# Pinguino-PIC18.net
KiCad netlist of a schematic drawn in EAGLE
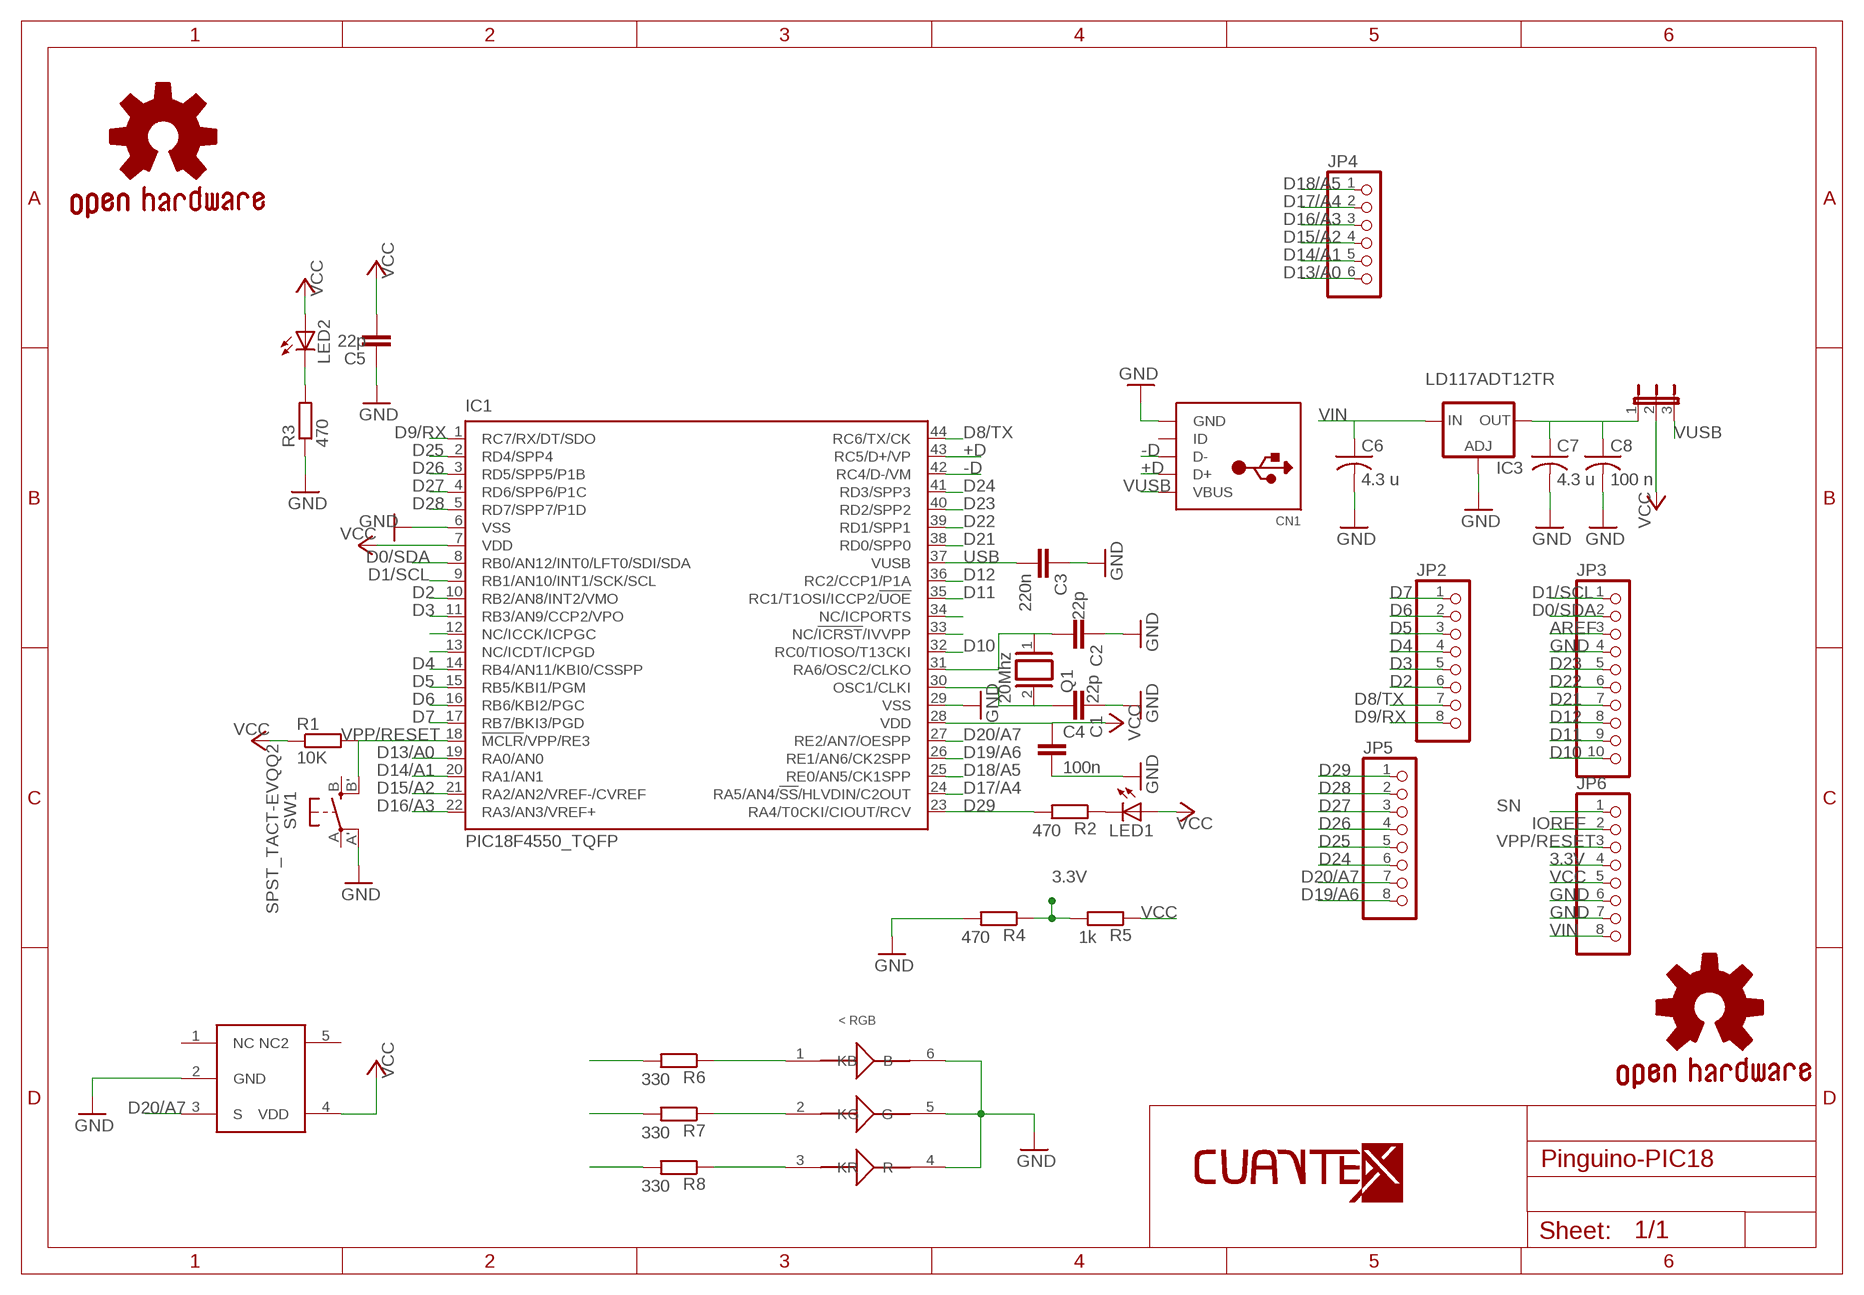
[diagram p0: schematic, sheet 1]

(export (version "E")
  (design (tool "Eeschema 10.0.6"))
  (components
    (comp (ref "C1")
      (value "22p")
      (footprint "eagle-import:C0603")
      (libsource (lib "eagle-import") (part "CC0603"))
    )
    (comp (ref "C2")
      (value "22p")
      (footprint "eagle-import:C0603")
      (libsource (lib "eagle-import") (part "CC0603"))
    )
    (comp (ref "C3")
      (value "220n")
      (footprint "eagle-import:C0603")
      (libsource (lib "eagle-import") (part "CC0603"))
    )
    (comp (ref "C4")
      (value "100n")
      (footprint "eagle-import:C0603")
      (libsource (lib "eagle-import") (part "CC0603"))
    )
    (comp (ref "C5")
      (value "22p")
      (footprint "eagle-import:C0603")
      (libsource (lib "eagle-import") (part "CC0603"))
    )
    (comp (ref "C6")
      (value "4.3 u")
      (footprint "eagle-import:C1206K")
      (libsource (lib "eagle-import") (part "C-USC1206K"))
    )
    (comp (ref "C7")
      (value "4.3 u")
      (footprint "eagle-import:C1206K")
      (libsource (lib "eagle-import") (part "C-USC1206K"))
    )
    (comp (ref "C8")
      (value "100 n")
      (footprint "eagle-import:C0603K")
      (libsource (lib "eagle-import") (part "C-USC0603K"))
    )
    (comp (ref "CN1")
      (value "USBMINIB")
      (footprint "eagle-import:USB-MINIB")
      (libsource (lib "eagle-import") (part "USBMINIB"))
    )
    (comp (ref "GOLD_ORB_SM1")
      (value "OSHWLOGO_GOLD_ORB_MED")
      (footprint "eagle-import:OSHW1")
      (libsource (lib "eagle-import") (part "OSHWLOGO_GOLD_ORB_MED"))
    )
    (comp (ref "GOLD_ORB_SM2")
      (value "OSHWLOGO_GOLD_ORB_SM")
      (footprint "eagle-import:OSHW2")
      (libsource (lib "eagle-import") (part "OSHWLOGO_GOLD_ORB_SM"))
    )
    (comp (ref "IC1")
      (value "PIC18F4550_TQFP")
      (footprint "eagle-import:TQFP44")
      (fields (field (name "MF") "MICROCHIP") (field (name "MPN") "PIC18F4550-I/PT"))
      (libsource (lib "eagle-import") (part "PIC18F4_TQFP550"))
    )
    (comp (ref "IC3")
      (value "LD117ADT12TR")
      (footprint "eagle-import:DPACK")
      (libsource (lib "eagle-import") (part "LD117A?DT12TR"))
    )
    (comp (ref "JP1")
      (value "JP2E")
      (footprint "eagle-import:JP2")
      (libsource (lib "eagle-import") (part "JP2E"))
    )
    (comp (ref "JP2")
      (value "PINHD-1X8")
      (footprint "eagle-import:1X08")
      (libsource (lib "eagle-import") (part "PINHD-1X8"))
    )
    (comp (ref "JP3")
      (value "PINHD-1X10")
      (footprint "eagle-import:1X10")
      (libsource (lib "eagle-import") (part "PINHD-1X10"))
    )
    (comp (ref "JP4")
      (value "PINHD-1X6")
      (footprint "eagle-import:1X06")
      (libsource (lib "eagle-import") (part "PINHD-1X6"))
    )
    (comp (ref "JP5")
      (value "PINHD-1X8")
      (footprint "eagle-import:1X08")
      (libsource (lib "eagle-import") (part "PINHD-1X8"))
    )
    (comp (ref "JP6")
      (value "PINHD-1X8")
      (footprint "eagle-import:1X08")
      (libsource (lib "eagle-import") (part "PINHD-1X8"))
    )
    (comp (ref "LED1")
      (value "LED_ESML0603")
      (footprint "eagle-import:LED_SML0603")
      (libsource (lib "eagle-import") (part "LED_ESML0603"))
    )
    (comp (ref "LED2")
      (value "LED_ESML0603")
      (footprint "eagle-import:LED_SML0603")
      (libsource (lib "eagle-import") (part "LED_ESML0603"))
    )
    (comp (ref "Q1")
      (value "20Mhz")
      (footprint "eagle-import:QS")
      (libsource (lib "eagle-import") (part "XTAL/S"))
    )
    (comp (ref "R1")
      (value "10K")
      (footprint "eagle-import:R0603")
      (libsource (lib "eagle-import") (part "RR0603"))
    )
    (comp (ref "R2")
      (value "470")
      (footprint "eagle-import:R0603")
      (libsource (lib "eagle-import") (part "RR0603"))
    )
    (comp (ref "R3")
      (value "470")
      (footprint "eagle-import:R0603")
      (libsource (lib "eagle-import") (part "RR0603"))
    )
    (comp (ref "R4")
      (value "470")
      (footprint "eagle-import:R0603")
      (libsource (lib "eagle-import") (part "RR0603"))
    )
    (comp (ref "R5")
      (value "1k")
      (footprint "eagle-import:R0603")
      (libsource (lib "eagle-import") (part "RR0603"))
    )
    (comp (ref "R6")
      (value "330")
      (footprint "eagle-import:R0603")
      (libsource (lib "eagle-import") (part "RR0603"))
    )
    (comp (ref "R7")
      (value "330")
      (footprint "eagle-import:R0603")
      (libsource (lib "eagle-import") (part "RR0603"))
    )
    (comp (ref "R8")
      (value "330")
      (footprint "eagle-import:R0603")
      (libsource (lib "eagle-import") (part "RR0603"))
    )
    (comp (ref "SW1")
      (value "SPST_TACT-EVQQ2")
      (footprint "eagle-import:EVQ-Q2")
      (libsource (lib "eagle-import") (part "SPST_TACT-EVQQ2"))
    )
    (comp (ref "U$1")
      (value "LOGO-TOP-30MM")
      (footprint "eagle-import:C-1")
      (libsource (lib "eagle-import") (part "LOGO-TOP-30MM"))
    )
    (comp (ref "U$3")
      (value "RGB_SMD")
      (footprint "eagle-import:SMD_LED")
      (libsource (lib "eagle-import") (part "RGB_SMD"))
    )
    (comp (ref "U$4")
      (value "SC70")
      (footprint "eagle-import:SC70")
      (libsource (lib "eagle-import") (part "SC70"))
    )
  )
  (nets
    (net (code "1") (name "/+D") (class "Default")
      (node (ref "CN1") (pin "D+") (pinfunction "D+_D+") (pintype "bidirectional"))
      (node (ref "IC1") (pin "43") (pinfunction "RC5/D+/VP_43") (pintype "bidirectional"))
    )
    (net (code "2") (name "/-D") (class "Default")
      (node (ref "CN1") (pin "D-") (pinfunction "D-_D-") (pintype "bidirectional"))
      (node (ref "IC1") (pin "42") (pinfunction "RC4/D-/VM_42") (pintype "bidirectional"))
    )
    (net (code "3") (name "/3.3V") (class "Default")
      (node (ref "JP6") (pin "4") (pinfunction "4_4") (pintype "passive"))
      (node (ref "R4") (pin "1") (pinfunction "1_1") (pintype "passive"))
      (node (ref "R5") (pin "2") (pinfunction "2_2") (pintype "passive"))
    )
    (net (code "4") (name "/AREF") (class "Default")
      (node (ref "JP3") (pin "3") (pinfunction "3_3") (pintype "passive"))
    )
    (net (code "5") (name "/D0{slash}SDA") (class "Default")
      (node (ref "IC1") (pin "8") (pinfunction "RB0/AN12/INT0/LFT0/SDI/SDA_8") (pintype "bidirectional"))
      (node (ref "JP3") (pin "2") (pinfunction "2_2") (pintype "passive"))
    )
    (net (code "6") (name "/D1{slash}SCL") (class "Default")
      (node (ref "IC1") (pin "9") (pinfunction "RB1/AN10/INT1/SCK/SCL_9") (pintype "bidirectional"))
      (node (ref "JP3") (pin "1") (pinfunction "1_1") (pintype "passive"))
    )
    (net (code "7") (name "/D2") (class "Default")
      (node (ref "IC1") (pin "10") (pinfunction "RB2/AN8/INT2/VMO_10") (pintype "bidirectional"))
      (node (ref "JP2") (pin "6") (pinfunction "6_6") (pintype "passive"))
    )
    (net (code "8") (name "/D3") (class "Default")
      (node (ref "IC1") (pin "11") (pinfunction "RB3/AN9/CCP2/VPO_11") (pintype "bidirectional"))
      (node (ref "JP2") (pin "5") (pinfunction "5_5") (pintype "passive"))
      (node (ref "R6") (pin "2") (pinfunction "2_2") (pintype "passive"))
    )
    (net (code "9") (name "/D4") (class "Default")
      (node (ref "IC1") (pin "14") (pinfunction "RB4/AN11/KBI0/CSSPP_14") (pintype "bidirectional"))
      (node (ref "JP2") (pin "4") (pinfunction "4_4") (pintype "passive"))
    )
    (net (code "10") (name "/D5") (class "Default")
      (node (ref "IC1") (pin "15") (pinfunction "RB5/KBI1/PGM_15") (pintype "bidirectional"))
      (node (ref "JP2") (pin "3") (pinfunction "3_3") (pintype "passive"))
    )
    (net (code "11") (name "/D6") (class "Default")
      (node (ref "IC1") (pin "16") (pinfunction "RB6/KBI2/PGC_16") (pintype "bidirectional"))
      (node (ref "JP2") (pin "2") (pinfunction "2_2") (pintype "passive"))
    )
    (net (code "12") (name "/D7") (class "Default")
      (node (ref "IC1") (pin "17") (pinfunction "RB7/BKI3/PGD_17") (pintype "bidirectional"))
      (node (ref "JP2") (pin "1") (pinfunction "1_1") (pintype "passive"))
    )
    (net (code "13") (name "/D8{slash}TX") (class "Default")
      (node (ref "IC1") (pin "44") (pinfunction "RC6/TX/CK_44") (pintype "bidirectional"))
      (node (ref "JP2") (pin "7") (pinfunction "7_7") (pintype "passive"))
    )
    (net (code "14") (name "/D9{slash}RX") (class "Default")
      (node (ref "IC1") (pin "1") (pinfunction "RC7/RX/DT/SDO_1") (pintype "bidirectional"))
      (node (ref "JP2") (pin "8") (pinfunction "8_8") (pintype "passive"))
    )
    (net (code "15") (name "/D10") (class "Default")
      (node (ref "IC1") (pin "32") (pinfunction "RC0/TIOSO/T13CKI_32") (pintype "bidirectional"))
      (node (ref "JP3") (pin "10") (pinfunction "10_10") (pintype "passive"))
    )
    (net (code "16") (name "/D11") (class "Default")
      (node (ref "IC1") (pin "35") (pinfunction "RC1/T1OSI/ICCP2/~{UOE}_35") (pintype "bidirectional"))
      (node (ref "JP3") (pin "9") (pinfunction "9_9") (pintype "passive"))
    )
    (net (code "17") (name "/D12") (class "Default")
      (node (ref "IC1") (pin "36") (pinfunction "RC2/CCP1/P1A_36") (pintype "bidirectional"))
      (node (ref "JP3") (pin "8") (pinfunction "8_8") (pintype "passive"))
      (node (ref "R7") (pin "2") (pinfunction "2_2") (pintype "passive"))
    )
    (net (code "18") (name "/D13{slash}A0") (class "Default")
      (node (ref "IC1") (pin "19") (pinfunction "RA0/AN0_19") (pintype "bidirectional"))
      (node (ref "JP4") (pin "6") (pinfunction "6_6") (pintype "passive"))
    )
    (net (code "19") (name "/D14{slash}A1") (class "Default")
      (node (ref "IC1") (pin "20") (pinfunction "RA1/AN1_20") (pintype "bidirectional"))
      (node (ref "JP4") (pin "5") (pinfunction "5_5") (pintype "passive"))
    )
    (net (code "20") (name "/D15{slash}A2") (class "Default")
      (node (ref "IC1") (pin "21") (pinfunction "RA2/AN2/VREF-/CVREF_21") (pintype "bidirectional"))
      (node (ref "JP4") (pin "4") (pinfunction "4_4") (pintype "passive"))
    )
    (net (code "21") (name "/D16{slash}A3") (class "Default")
      (node (ref "IC1") (pin "22") (pinfunction "RA3/AN3/VREF+_22") (pintype "bidirectional"))
      (node (ref "JP4") (pin "3") (pinfunction "3_3") (pintype "passive"))
    )
    (net (code "22") (name "/D17{slash}A4") (class "Default")
      (node (ref "IC1") (pin "24") (pinfunction "RA5/AN4/~{SS}/HLVDIN/C2OUT_24") (pintype "bidirectional"))
      (node (ref "JP4") (pin "2") (pinfunction "2_2") (pintype "passive"))
    )
    (net (code "23") (name "/D18{slash}A5") (class "Default")
      (node (ref "IC1") (pin "25") (pinfunction "RE0/AN5/CK1SPP_25") (pintype "bidirectional"))
      (node (ref "JP4") (pin "1") (pinfunction "1_1") (pintype "passive"))
    )
    (net (code "24") (name "/D19{slash}A6") (class "Default")
      (node (ref "IC1") (pin "26") (pinfunction "RE1/AN6/CK2SPP_26") (pintype "bidirectional"))
      (node (ref "JP5") (pin "8") (pinfunction "8_8") (pintype "passive"))
    )
    (net (code "25") (name "/D20{slash}A7") (class "Default")
      (node (ref "IC1") (pin "27") (pinfunction "RE2/AN7/OESPP_27") (pintype "bidirectional"))
      (node (ref "JP5") (pin "7") (pinfunction "7_7") (pintype "passive"))
      (node (ref "U$4") (pin "3") (pinfunction "S_3") (pintype "bidirectional"))
    )
    (net (code "26") (name "/D21") (class "Default")
      (node (ref "IC1") (pin "38") (pinfunction "RD0/SPP0_38") (pintype "bidirectional"))
      (node (ref "JP3") (pin "7") (pinfunction "7_7") (pintype "passive"))
      (node (ref "R8") (pin "2") (pinfunction "2_2") (pintype "passive"))
    )
    (net (code "27") (name "/D22") (class "Default")
      (node (ref "IC1") (pin "39") (pinfunction "RD1/SPP1_39") (pintype "bidirectional"))
      (node (ref "JP3") (pin "6") (pinfunction "6_6") (pintype "passive"))
    )
    (net (code "28") (name "/D23") (class "Default")
      (node (ref "IC1") (pin "40") (pinfunction "RD2/SPP2_40") (pintype "bidirectional"))
      (node (ref "JP3") (pin "5") (pinfunction "5_5") (pintype "passive"))
    )
    (net (code "29") (name "/D24") (class "Default")
      (node (ref "IC1") (pin "41") (pinfunction "RD3/SPP3_41") (pintype "bidirectional"))
      (node (ref "JP5") (pin "6") (pinfunction "6_6") (pintype "passive"))
    )
    (net (code "30") (name "/D25") (class "Default")
      (node (ref "IC1") (pin "2") (pinfunction "RD4/SPP4_2") (pintype "bidirectional"))
      (node (ref "JP5") (pin "5") (pinfunction "5_5") (pintype "passive"))
    )
    (net (code "31") (name "/D26") (class "Default")
      (node (ref "IC1") (pin "3") (pinfunction "RD5/SPP5/P1B_3") (pintype "bidirectional"))
      (node (ref "JP5") (pin "4") (pinfunction "4_4") (pintype "passive"))
    )
    (net (code "32") (name "/D27") (class "Default")
      (node (ref "IC1") (pin "4") (pinfunction "RD6/SPP6/P1C_4") (pintype "bidirectional"))
      (node (ref "JP5") (pin "3") (pinfunction "3_3") (pintype "passive"))
    )
    (net (code "33") (name "/D28") (class "Default")
      (node (ref "IC1") (pin "5") (pinfunction "RD7/SPP7/P1D_5") (pintype "bidirectional"))
      (node (ref "JP5") (pin "2") (pinfunction "2_2") (pintype "passive"))
    )
    (net (code "34") (name "/D29") (class "Default")
      (node (ref "IC1") (pin "23") (pinfunction "RA4/T0CKI/CIOUT/RCV_23") (pintype "bidirectional"))
      (node (ref "JP5") (pin "1") (pinfunction "1_1") (pintype "passive"))
      (node (ref "R2") (pin "2") (pinfunction "2_2") (pintype "passive"))
    )
    (net (code "35") (name "/IOREF") (class "Default")
      (node (ref "JP6") (pin "2") (pinfunction "2_2") (pintype "passive"))
    )
    (net (code "36") (name "/SN") (class "Default")
      (node (ref "JP6") (pin "1") (pinfunction "1_1") (pintype "passive"))
    )
    (net (code "37") (name "/USB") (class "Default")
      (node (ref "C3") (pin "2") (pinfunction "2_2") (pintype "passive"))
      (node (ref "IC1") (pin "37") (pinfunction "VUSB_37") (pintype "bidirectional"))
    )
    (net (code "38") (name "/VIN") (class "Default")
      (node (ref "C6") (pin "1") (pinfunction "1_1") (pintype "passive"))
      (node (ref "IC3") (pin "3") (pinfunction "IN_3") (pintype "input"))
      (node (ref "JP6") (pin "8") (pinfunction "8_8") (pintype "passive"))
    )
    (net (code "39") (name "/VPP{slash}RESET") (class "Default")
      (node (ref "IC1") (pin "18") (pinfunction "~{MCLR}/VPP/RE3_18") (pintype "input"))
      (node (ref "JP6") (pin "3") (pinfunction "3_3") (pintype "passive"))
      (node (ref "R1") (pin "2") (pinfunction "2_2") (pintype "passive"))
      (node (ref "SW1") (pin "B'") (pinfunction "S1_B'") (pintype "passive"))
    )
    (net (code "40") (name "/VUSB") (class "Default")
      (node (ref "CN1") (pin "VBUS") (pinfunction "VBUS_VBUS") (pintype "power_in"))
      (node (ref "JP1") (pin "3") (pinfunction "3_3") (pintype "passive"))
    )
    (net (code "41") (name "GND") (class "Default")
      (node (ref "C1") (pin "1") (pinfunction "1_1") (pintype "passive"))
      (node (ref "C2") (pin "1") (pinfunction "1_1") (pintype "passive"))
      (node (ref "C3") (pin "1") (pinfunction "1_1") (pintype "passive"))
      (node (ref "C4") (pin "2") (pinfunction "2_2") (pintype "passive"))
      (node (ref "C5") (pin "1") (pinfunction "1_1") (pintype "passive"))
      (node (ref "C6") (pin "2") (pinfunction "2_2") (pintype "passive"))
      (node (ref "C7") (pin "2") (pinfunction "2_2") (pintype "passive"))
      (node (ref "C8") (pin "2") (pinfunction "2_2") (pintype "passive"))
      (node (ref "CN1") (pin "GND") (pinfunction "GND_GND") (pintype "power_in"))
      (node (ref "IC1") (pin "29") (pinfunction "VSS_29") (pintype "power_in"))
      (node (ref "IC1") (pin "6") (pinfunction "VSS_6") (pintype "power_in"))
      (node (ref "IC3") (pin "1") (pinfunction "ADJ_1") (pintype "input"))
      (node (ref "JP3") (pin "4") (pinfunction "4_4") (pintype "passive"))
      (node (ref "JP6") (pin "6") (pinfunction "6_6") (pintype "passive"))
      (node (ref "JP6") (pin "7") (pinfunction "7_7") (pintype "passive"))
      (node (ref "R3") (pin "1") (pinfunction "1_1") (pintype "passive"))
      (node (ref "R4") (pin "2") (pinfunction "2_2") (pintype "passive"))
      (node (ref "SW1") (pin "A'") (pinfunction "P1_A'") (pintype "passive"))
      (node (ref "U$3") (pin "4") (pinfunction "R_4") (pintype "bidirectional"))
      (node (ref "U$3") (pin "5") (pinfunction "G_5") (pintype "bidirectional"))
      (node (ref "U$3") (pin "6") (pinfunction "B_6") (pintype "bidirectional"))
      (node (ref "U$4") (pin "2") (pinfunction "GND_2") (pintype "bidirectional"))
    )
    (net (code "42") (name "Net-(IC1-OSC1{slash}CLKI)") (class "Default")
      (node (ref "C1") (pin "2") (pinfunction "2_2") (pintype "passive"))
      (node (ref "IC1") (pin "30") (pinfunction "OSC1/CLKI_30") (pintype "input"))
      (node (ref "Q1") (pin "2") (pinfunction "2_2") (pintype "passive"))
    )
    (net (code "43") (name "Net-(IC1-RA6{slash}OSC2{slash}CLKO)") (class "Default")
      (node (ref "C2") (pin "2") (pinfunction "2_2") (pintype "passive"))
      (node (ref "IC1") (pin "31") (pinfunction "RA6/OSC2/CLKO_31") (pintype "output"))
      (node (ref "Q1") (pin "1") (pinfunction "1_1") (pintype "passive"))
    )
    (net (code "44") (name "Net-(IC3-OUT)") (class "Default")
      (node (ref "C7") (pin "1") (pinfunction "1_1") (pintype "passive"))
      (node (ref "C8") (pin "1") (pinfunction "1_1") (pintype "passive"))
      (node (ref "IC3") (pin "4") (pinfunction "OUT_4") (pintype "passive"))
      (node (ref "JP1") (pin "1") (pinfunction "1_1") (pintype "passive"))
    )
    (net (code "45") (name "Net-(LED1-PadC)") (class "Default")
      (node (ref "LED1") (pin "C") (pinfunction "C_C") (pintype "passive"))
      (node (ref "R2") (pin "1") (pinfunction "1_1") (pintype "passive"))
    )
    (net (code "46") (name "Net-(LED2-PadC)") (class "Default")
      (node (ref "LED2") (pin "C") (pinfunction "C_C") (pintype "passive"))
      (node (ref "R3") (pin "2") (pinfunction "2_2") (pintype "passive"))
    )
    (net (code "47") (name "Net-(U$3-KB)") (class "Default")
      (node (ref "R6") (pin "1") (pinfunction "1_1") (pintype "passive"))
      (node (ref "U$3") (pin "1") (pinfunction "KB_1") (pintype "bidirectional"))
    )
    (net (code "48") (name "Net-(U$3-KG)") (class "Default")
      (node (ref "R7") (pin "1") (pinfunction "1_1") (pintype "passive"))
      (node (ref "U$3") (pin "2") (pinfunction "KG_2") (pintype "bidirectional"))
    )
    (net (code "49") (name "Net-(U$3-KR)") (class "Default")
      (node (ref "R8") (pin "1") (pinfunction "1_1") (pintype "passive"))
      (node (ref "U$3") (pin "3") (pinfunction "KR_3") (pintype "bidirectional"))
    )
    (net (code "50") (name "VCC") (class "Default")
      (node (ref "C4") (pin "1") (pinfunction "1_1") (pintype "passive"))
      (node (ref "C5") (pin "2") (pinfunction "2_2") (pintype "passive"))
      (node (ref "IC1") (pin "28") (pinfunction "VDD_28") (pintype "power_in"))
      (node (ref "IC1") (pin "7") (pinfunction "VDD_7") (pintype "power_in"))
      (node (ref "JP1") (pin "2") (pinfunction "2_2") (pintype "passive"))
      (node (ref "JP6") (pin "5") (pinfunction "5_5") (pintype "passive"))
      (node (ref "LED1") (pin "A") (pinfunction "A_A") (pintype "passive"))
      (node (ref "LED2") (pin "A") (pinfunction "A_A") (pintype "passive"))
      (node (ref "R1") (pin "1") (pinfunction "1_1") (pintype "passive"))
      (node (ref "R5") (pin "1") (pinfunction "1_1") (pintype "passive"))
      (node (ref "U$4") (pin "4") (pinfunction "VDD_4") (pintype "bidirectional"))
    )
    (net (code "51") (name "unconnected-(CN1-PadID)") (class "Default")
      (node (ref "CN1") (pin "ID") (pinfunction "ID_ID") (pintype "bidirectional"))
    )
    (net (code "52") (name "unconnected-(IC1-NC{slash}ICCK{slash}ICPGC-Pad12)") (class "Default")
      (node (ref "IC1") (pin "12") (pinfunction "NC/ICCK/ICPGC_12") (pintype "bidirectional"))
    )
    (net (code "53") (name "unconnected-(IC1-NC{slash}ICDT{slash}ICPGD-Pad13)") (class "Default")
      (node (ref "IC1") (pin "13") (pinfunction "NC/ICDT/ICPGD_13") (pintype "bidirectional"))
    )
    (net (code "54") (name "unconnected-(IC1-NC{slash}ICPORTS-Pad34)") (class "Default")
      (node (ref "IC1") (pin "34") (pinfunction "NC/ICPORTS_34") (pintype "input"))
    )
    (net (code "55") (name "unconnected-(IC1-NC{slash}~{ICRST}{slash}IVVPP-Pad33)") (class "Default")
      (node (ref "IC1") (pin "33") (pinfunction "NC/~{ICRST}/IVVPP_33") (pintype "input"))
    )
    (net (code "56") (name "unconnected-(SW1-P-PadA)") (class "Default")
      (node (ref "SW1") (pin "A") (pinfunction "P_A") (pintype "passive"))
    )
    (net (code "57") (name "unconnected-(SW1-S-PadB)") (class "Default")
      (node (ref "SW1") (pin "B") (pinfunction "S_B") (pintype "passive"))
    )
    (net (code "58") (name "unconnected-(U$4-NC-Pad1)") (class "Default")
      (node (ref "U$4") (pin "1") (pinfunction "NC_1") (pintype "bidirectional"))
    )
    (net (code "59") (name "unconnected-(U$4-NC2-Pad5)") (class "Default")
      (node (ref "U$4") (pin "5") (pinfunction "NC2_5") (pintype "bidirectional"))
    )
  )
)
